# Load-Network.net
KiCad netlist of a schematic drawn in Altium Designer
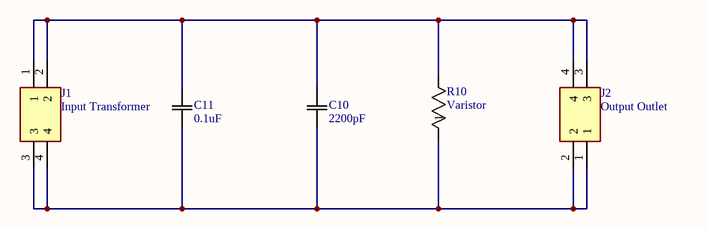
[diagram p0: Load-Network.SchDoc]

(export (version "E")
  (design (tool "Eeschema 10.0.6"))
  (components
    (comp (ref "C10")
      (value "2200pF")
      (footprint "CAP_B81123C1222M289_TDK")
      (description "No Description Available")
      (fields
        (field (name "MANUFACTURER_PART_NUMBER") "B81123C1222M289")
        (field (name "COPYRIGHT") "Copyright (C) 2022 Ultra Librarian. All rights reserved.")
      )
      (libsource (lib "2200pF-HV-Ind") (part "B81123C1222M289"))
    )
    (comp (ref "C11")
      (value "0.1uF")
      (footprint "CAPM24X11.3_20.3_1_VIS")
      (description "No Description Available")
      (fields
        (field (name "MANUFACTURER_PART_NUMBER") "PME261JC6100KR19T0")
        (field (name "COPYRIGHT") "Copyright (C) 2022 Ultra Librarian. All rights reserved.")
      )
      (libsource (lib "0.1uF-HV-Ind") (part "PME261JC6100KR19T0"))
    )
    (comp (ref "J1")
      (value "Input Transformer")
      (footprint "SamacSys:1709681")
      (description "Connector")
      (fields
        (field (name "MOUSER2 PART NUMBER") "651-1709681")
        (field (name "MANUFACTURER_PART_NUMBER") "1709681")
      )
      (libsource (lib "") (part "1709681_1"))
    )
    (comp (ref "J2")
      (value "Output Outlet")
      (footprint "SamacSys:1709681")
      (description "Connector")
      (fields
        (field (name "MOUSER2 PART NUMBER") "651-1709681")
        (field (name "MANUFACTURER_PART_NUMBER") "1709681")
      )
      (libsource (lib "*") (part "1709681"))
    )
    (comp (ref "R10")
      (value "Varistor")
      (footprint "RES_VE24_AVX")
      (description "No Description Available")
      (fields
        (field (name "MANUFACTURER_PART_NUMBER") "VE24P00511K--")
        (field (name "COPYRIGHT") "Copyright (C) 2022 Ultra Librarian. All rights reserved.")
      )
      (libsource (lib "Varistor") (part "VE24P00511K--"))
    )
  )
  (nets
    (net (code "1") (name "Net-(C10-Pad1)") (class "Default")
      (node (ref "C10") (pin "1") (pinfunction "1_1") (pintype "passive"))
      (node (ref "C11") (pin "1") (pinfunction "1_1") (pintype "passive"))
      (node (ref "J1") (pin "3") (pinfunction "3_3") (pintype "passive"))
      (node (ref "J1") (pin "4") (pinfunction "4_4") (pintype "passive"))
      (node (ref "J2") (pin "1") (pinfunction "1_1") (pintype "passive"))
      (node (ref "J2") (pin "2") (pinfunction "2_2") (pintype "passive"))
      (node (ref "R10") (pin "1") (pinfunction "1_1") (pintype "passive"))
    )
    (net (code "2") (name "Net-(C10-Pad2)") (class "Default")
      (node (ref "C10") (pin "2") (pinfunction "2_2") (pintype "passive"))
      (node (ref "C11") (pin "2") (pinfunction "2_2") (pintype "passive"))
      (node (ref "J1") (pin "1") (pinfunction "1_1") (pintype "passive"))
      (node (ref "J1") (pin "2") (pinfunction "2_2") (pintype "passive"))
      (node (ref "J2") (pin "3") (pinfunction "3_3") (pintype "passive"))
      (node (ref "J2") (pin "4") (pinfunction "4_4") (pintype "passive"))
      (node (ref "R10") (pin "2") (pinfunction "2_2") (pintype "passive"))
    )
  )
)
